# Booster_scheme.net
KiCad netlist of a schematic drawn in Altium Designer
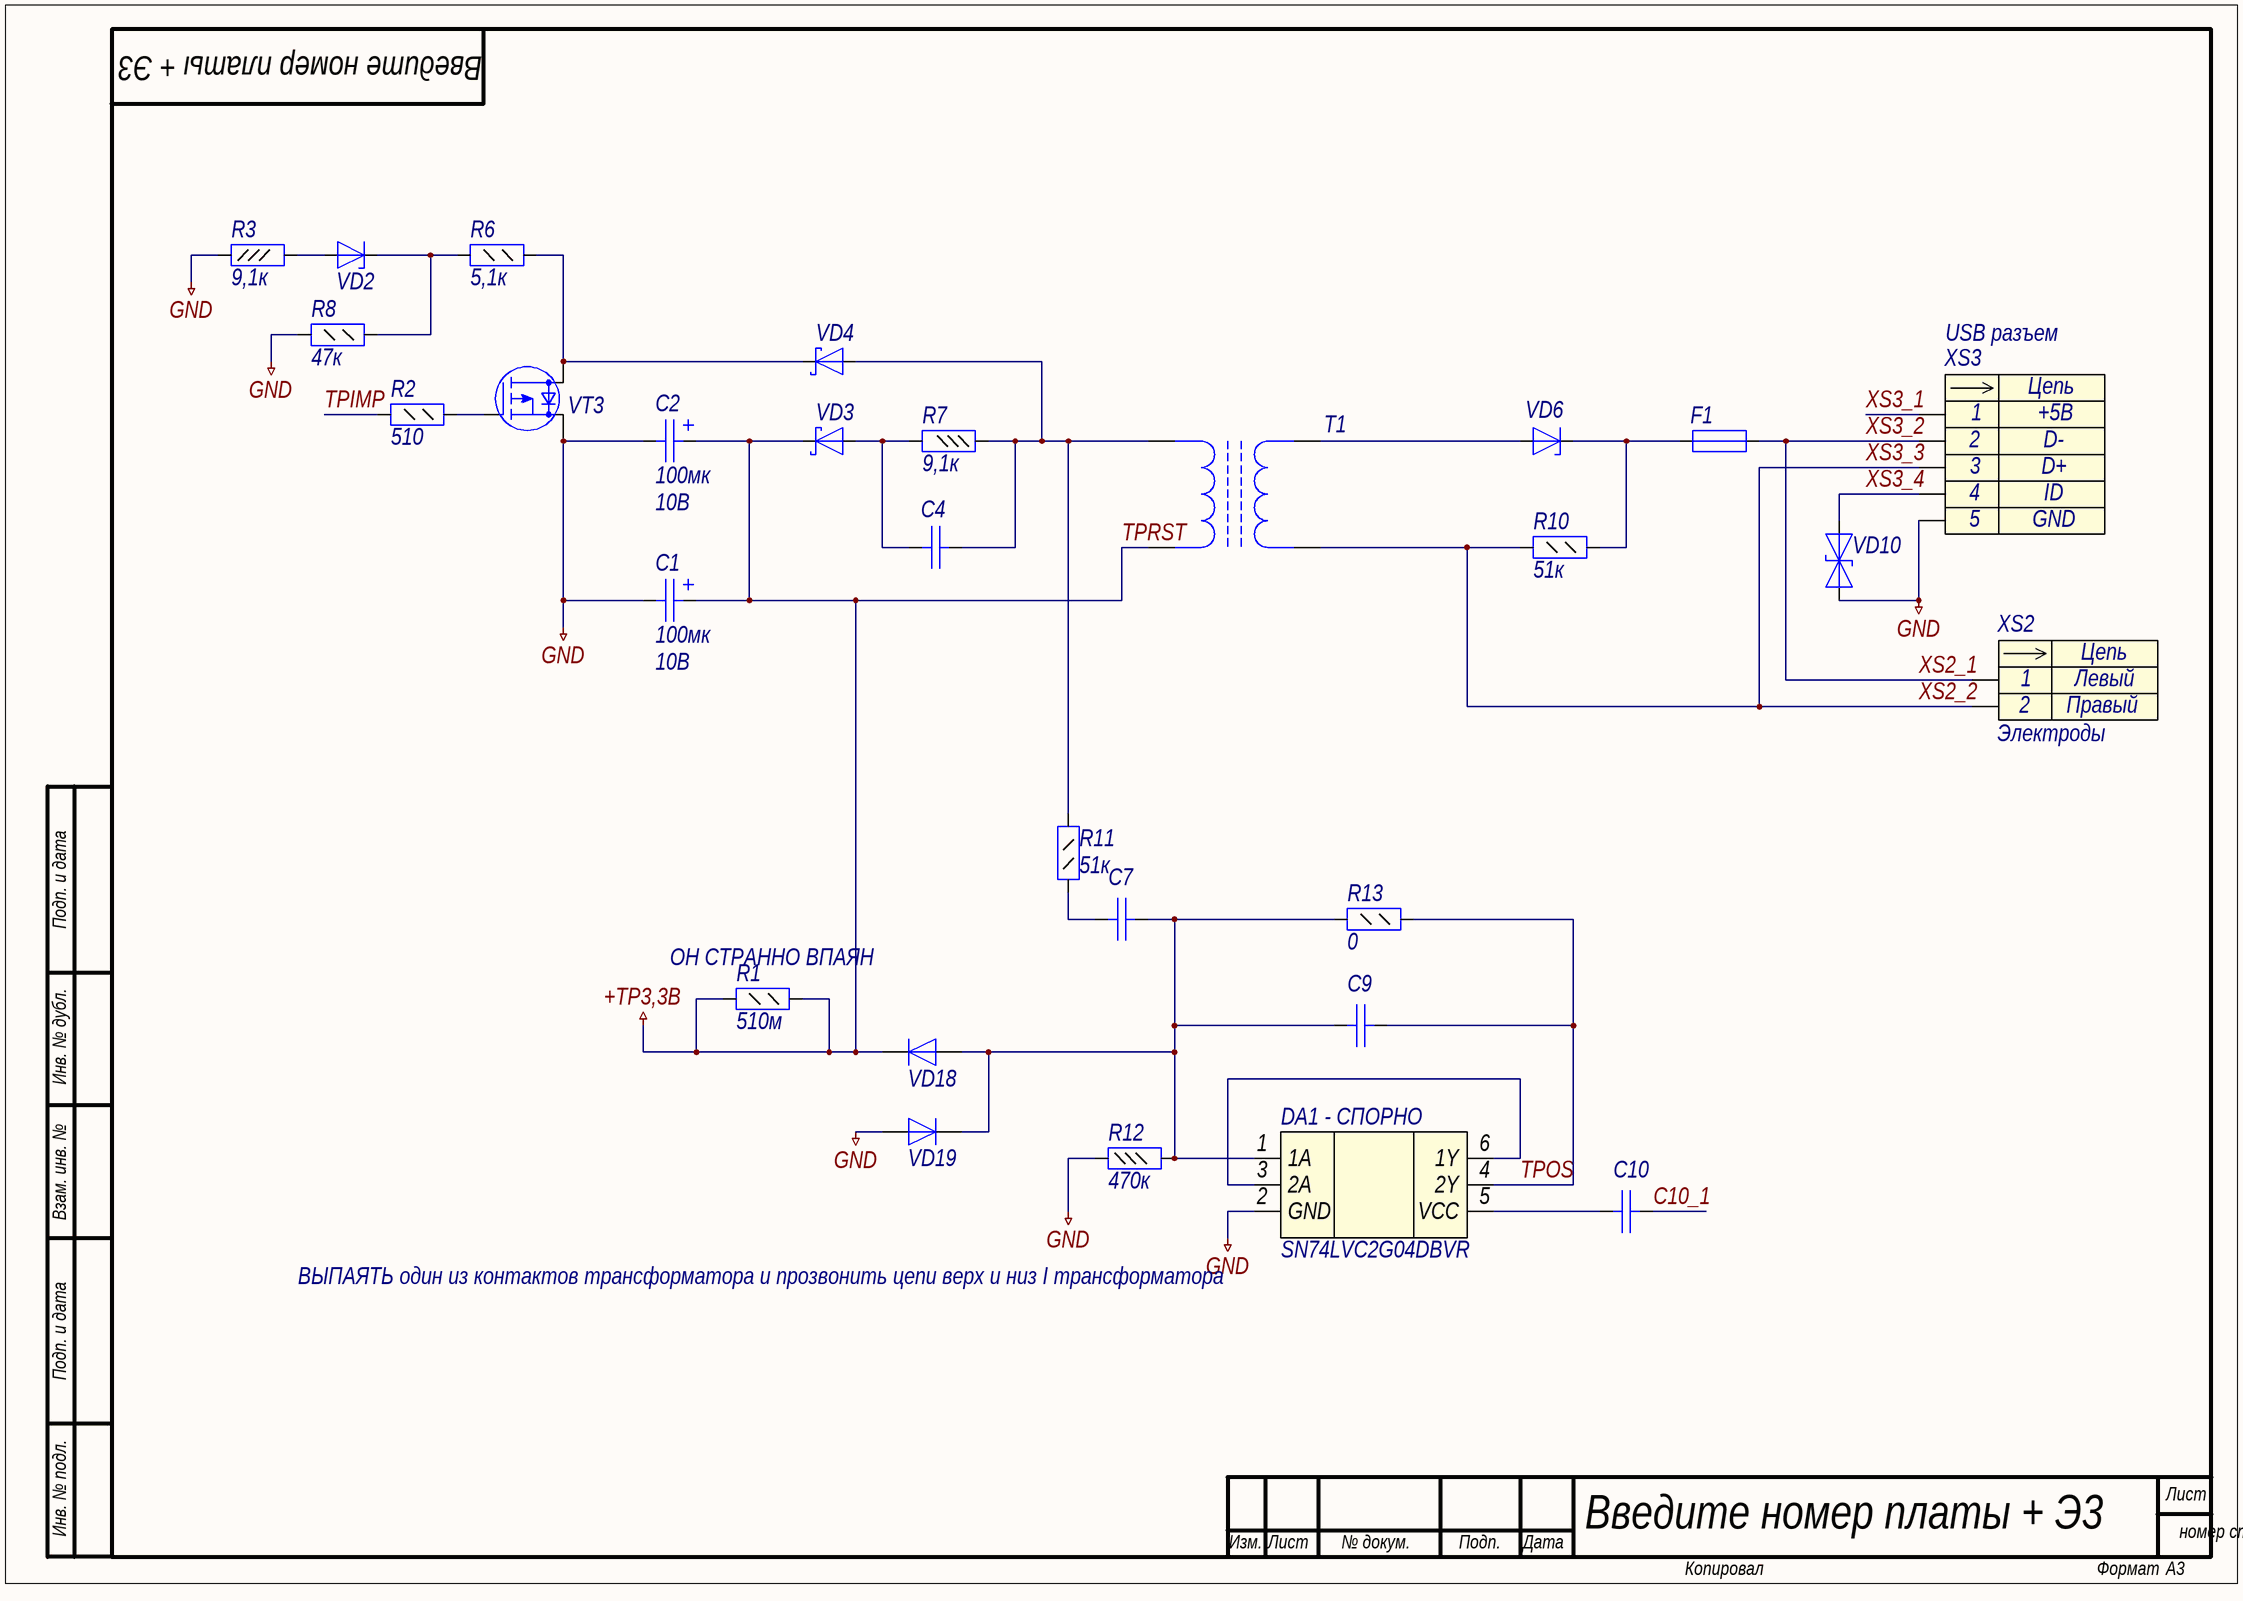
[diagram p0: Booster_scheme.SchDoc]

(export (version "E")
  (design (tool "Eeschema 10.0.6"))
  (components
    (comp (ref "C1")
      (value "100мк")
      (footprint "TANTAL CASE D")
      (description "Конденсатор полярный")
      (fields
        (field (name "VOLTAGE") "10В")
        (field (name "PART NUMBER") "T495D107K010ATA080")
        (field (name "Comment") "Capacitor_pol")
      )
      (libsource (lib "MOP44") (part "Capacitor_pol"))
    )
    (comp (ref "C2")
      (value "100мк")
      (footprint "TANTAL CASE D")
      (description "Конденсатор полярный")
      (fields
        (field (name "VOLTAGE") "10В")
        (field (name "PART NUMBER") "T495D107K010ATA080")
        (field (name "Comment") "Capacitor_pol")
      )
      (libsource (lib "MOP44") (part "Capacitor_pol"))
    )
    (comp (ref "C4")
      (value "Capacitor")
      (footprint "C0402")
      (description "Конденсатор")
      (fields (field (name "VOLTAGE") "50B") (field (name "PART NUMBER") "GRP1555C1HR47CZ01E"))
      (libsource (lib "MOP44") (part "Capacitor"))
    )
    (comp (ref "C7")
      (value "Capacitor")
      (footprint "C0402")
      (description "Конденсатор")
      (fields (field (name "VOLTAGE") "50B") (field (name "PART NUMBER") "GRP1555C1HR47CZ01E"))
      (libsource (lib "MOP44") (part "Capacitor"))
    )
    (comp (ref "C9")
      (value "Capacitor")
      (footprint "C0402")
      (description "Конденсатор")
      (fields (field (name "VOLTAGE") "50B") (field (name "PART NUMBER") "GRP1555C1HR47CZ01E"))
      (libsource (lib "MOP44") (part "Capacitor"))
    )
    (comp (ref "C10")
      (value "Capacitor")
      (footprint "C0402")
      (description "Конденсатор")
      (fields (field (name "VOLTAGE") "50B") (field (name "PART NUMBER") "GRP1555C1HR47CZ01E"))
      (libsource (lib "MOP44") (part "Capacitor"))
    )
    (comp (ref "DA1 - СПОРНО")
      (value "SN74LVC2G04DBVR")
      (footprint "SOT23-6")
      (description "Инвертирующий Триггер Шмитта")
      (fields (field (name "PART NUMBER") "SN74LVC2G04DBVR"))
      (libsource (lib "MOP44") (part "SN74LVC2G04DBVR"))
    )
    (comp (ref "F1")
      (value "Fuse")
      (footprint "FUSE812")
      (description "Предохранитель")
      (fields (field (name "PART NUMBER") "MF-MSMF050"))
      (libsource (lib "MOP44") (part "Fuse"))
    )
    (comp (ref "R1")
      (value "510м")
      (footprint "R0805")
      (description "Резистор")
      (fields (field (name "PART NUMBER") "RC0805FR-07510RL") (field (name "POWER") "0,125Вт"))
      (libsource (lib "MOP44") (part "Resistor_0,125Вт"))
    )
    (comp (ref "R2")
      (value "510")
      (footprint "R0805")
      (description "Резистор")
      (fields (field (name "PART NUMBER") "RC0805FR-07510RL") (field (name "POWER") "0,125Вт"))
      (libsource (lib "MOP44") (part "Resistor_0,125Вт"))
    )
    (comp (ref "R3")
      (value "9,1к")
      (footprint "R0603")
      (description "Резистор")
      (fields (field (name "PART NUMBER") "RC0603FR-079K1") (field (name "POWER") "0,062Вт"))
      (libsource (lib "") (part "Resistor_0,062Вт_1"))
    )
    (comp (ref "R6")
      (value "5,1к")
      (footprint "R0805")
      (description "Резистор")
      (fields (field (name "PART NUMBER") "RC0805FR-075K1") (field (name "POWER") "0,125Вт"))
      (libsource (lib "MOP44") (part "Resistor_0,125Вт"))
    )
    (comp (ref "R7")
      (value "9,1к")
      (footprint "R0603")
      (description "Резистор")
      (fields (field (name "PART NUMBER") "RC0603FR-079K1") (field (name "POWER") "0,062Вт"))
      (libsource (lib "") (part "Resistor_0,062Вт_2"))
    )
    (comp (ref "R8")
      (value "47к")
      (footprint "R0805")
      (description "Резистор")
      (fields (field (name "PART NUMBER") "RC0805FR-0747KL") (field (name "POWER") "0,125Вт"))
      (libsource (lib "MOP44") (part "Resistor_0,125Вт"))
    )
    (comp (ref "R10")
      (value "51к")
      (footprint "R0805")
      (description "Резистор")
      (fields (field (name "PART NUMBER") "RC0805FR-0751KL") (field (name "POWER") "0,125Вт"))
      (libsource (lib "MOP44") (part "Resistor_0,125Вт"))
    )
    (comp (ref "R11")
      (value "51к")
      (footprint "R0805")
      (description "Резистор")
      (fields (field (name "PART NUMBER") "RC0805FR-0751KL") (field (name "POWER") "0,125Вт"))
      (libsource (lib "") (part "Resistor_0,125Вт_1"))
    )
    (comp (ref "R12")
      (value "470к")
      (footprint "R0603")
      (description "Резистор")
      (fields (field (name "PART NUMBER") "RC0603FR-07470KL") (field (name "POWER") "0,062Вт"))
      (libsource (lib "MOP44") (part "Resistor_0,062Вт"))
    )
    (comp (ref "R13")
      (value "0")
      (footprint "R0805")
      (description "Резистор")
      (fields (field (name "PART NUMBER") "RC0805FR-070RL") (field (name "POWER") "0,125Вт"))
      (libsource (lib "MOP44") (part "Resistor_0,125Вт"))
    )
    (comp (ref "T1")
      (value "Transformer")
      (footprint "Transformer36mm")
      (description "EMI Suppression Filter")
      (libsource (lib "MOP44") (part "Transformer"))
    )
    (comp (ref "VD2")
      (value "DiodeZener")
      (footprint "SOT23-3")
      (description "Cтабилитрон (лавинный выпрямительный диод) односторонний")
      (fields (field (name "PART NUMBER") "BZX84-C30"))
      (libsource (lib "MOP44") (part "DiodeZener"))
    )
    (comp (ref "VD3")
      (value "DiodeSchottky")
      (footprint "SOD-123")
      (description "Диод Шоттки")
      (fields (field (name "PART NUMBER") "MBR0540"))
      (libsource (lib "MOP44") (part "DiodeSchottky"))
    )
    (comp (ref "VD4")
      (value "DiodeSchottky")
      (footprint "SOD-123")
      (description "Диод Шоттки")
      (fields (field (name "PART NUMBER") "MBR0540"))
      (libsource (lib "MOP44") (part "DiodeSchottky"))
    )
    (comp (ref "VD6")
      (value "DiodeZener")
      (footprint "SOT23-3")
      (description "Cтабилитрон (лавинный выпрямительный диод) односторонний")
      (fields (field (name "PART NUMBER") "BZX84-C5V1"))
      (libsource (lib "MOP44") (part "DiodeZener"))
    )
    (comp (ref "VD10")
      (value "DiodeZenerDual")
      (footprint "SMB")
      (description "Cтабилитрон (диод выпрямительный лавинный) двусторонний")
      (fields (field (name "PART NUMBER") "SMBJ8.5CA"))
      (libsource (lib "MOP44") (part "DiodeZenerDual"))
    )
    (comp (ref "VD18")
      (value "Diode")
      (footprint "SOD-123")
      (description "Диод")
      (fields (field (name "PART NUMBER") "MMSD4148"))
      (libsource (lib "MOP44") (part "Diode"))
    )
    (comp (ref "VD19")
      (value "Diode")
      (footprint "SOD-123")
      (description "Диод")
      (fields (field (name "PART NUMBER") "MMSD4148"))
      (libsource (lib "MOP44") (part "Diode"))
    )
    (comp (ref "VT3")
      (value "P-MOSFET")
      (footprint "SOT23-3")
      (description "N-MOSFET")
      (fields
        (field (name "PART NUMBER") "IRLML2244TRPbF")
        (field (name "MANUFACTURER") "International Rectifier")
      )
      (libsource (lib "MOP44") (part "P-MOSFET"))
    )
    (comp (ref "XS2")
      (value "Электроды")
      (footprint "CWF-2")
      (description "Разъем - 2 конт. вилка")
      (fields (field (name "PART NUMBER") "DS1069-2MVW6X"))
      (libsource (lib "MOP44") (part "Header_2_plg"))
    )
    (comp (ref "XS3")
      (value "USB разъем")
      (footprint "USB MINI AB RECEPTACLE")
      (description "USB Mini Type AB Receptacle")
      (fields (field (name "PART NUMBER") "UJ2-MABH-1-SMT-TR"))
      (libsource (lib "MOP44") (part "USB MINI RECEPTACLE"))
    )
  )
  (nets
    (net (code "1") (name "+TP3,3В") (class "Default")
      (node (ref "C1") (pin "1") (pinfunction "1_1") (pintype "passive"))
      (node (ref "C2") (pin "1") (pinfunction "1_1") (pintype "passive"))
      (node (ref "R1") (pin "1") (pinfunction "1_1") (pintype "passive"))
      (node (ref "R1") (pin "2") (pinfunction "2_2") (pintype "passive"))
      (node (ref "T1") (pin "2") (pinfunction "2_2") (pintype "passive"))
      (node (ref "VD18") (pin "1") (pinfunction "K_1") (pintype "passive"))
      (node (ref "VD3") (pin "1") (pinfunction "K_1") (pintype "passive"))
    )
    (net (code "2") (name "/C10_1") (class "Default")
      (node (ref "C10") (pin "1") (pinfunction "1_1") (pintype "passive"))
    )
    (net (code "3") (name "/TPIMP") (class "Default")
      (node (ref "R2") (pin "2") (pinfunction "2_2") (pintype "passive"))
    )
    (net (code "4") (name "/TPOS") (class "Default")
      (node (ref "C9") (pin "2") (pinfunction "2_2") (pintype "passive"))
      (node (ref "DA1 - СПОРНО") (pin "4") (pinfunction "2Y_4") (pintype "power_in"))
      (node (ref "R13") (pin "1") (pinfunction "1_1") (pintype "passive"))
    )
    (net (code "5") (name "/XS2_1") (class "Default")
      (node (ref "F1") (pin "1") (pinfunction "1_1") (pintype "passive"))
      (node (ref "XS2") (pin "1") (pinfunction "1_1") (pintype "passive"))
      (node (ref "XS3") (pin "2") (pinfunction "2_2") (pintype "passive"))
    )
    (net (code "6") (name "/XS2_2") (class "Default")
      (node (ref "R10") (pin "2") (pinfunction "2_2") (pintype "passive"))
      (node (ref "T1") (pin "4") (pinfunction "4_4") (pintype "passive"))
      (node (ref "XS2") (pin "2") (pinfunction "2_2") (pintype "passive"))
      (node (ref "XS3") (pin "3") (pinfunction "3_3") (pintype "passive"))
    )
    (net (code "7") (name "/XS3_1") (class "Default")
      (node (ref "XS3") (pin "1") (pinfunction "1_1") (pintype "passive"))
    )
    (net (code "8") (name "/XS3_4") (class "Default")
      (node (ref "VD10") (pin "2") (pinfunction "A_2") (pintype "passive"))
      (node (ref "XS3") (pin "4") (pinfunction "4_4") (pintype "passive"))
    )
    (net (code "9") (name "GND") (class "Default")
      (node (ref "C1") (pin "2") (pinfunction "2_2") (pintype "passive"))
      (node (ref "C2") (pin "2") (pinfunction "2_2") (pintype "passive"))
      (node (ref "DA1 - СПОРНО") (pin "2") (pinfunction "GND_2") (pintype "power_in"))
      (node (ref "R12") (pin "1") (pinfunction "1_1") (pintype "passive"))
      (node (ref "R3") (pin "1") (pinfunction "1_1") (pintype "passive"))
      (node (ref "R8") (pin "2") (pinfunction "2_2") (pintype "passive"))
      (node (ref "VD10") (pin "1") (pinfunction "K_1") (pintype "passive"))
      (node (ref "VD19") (pin "2") (pinfunction "A_2") (pintype "passive"))
      (node (ref "VT3") (pin "3") (pinfunction "S_3") (pintype "passive"))
      (node (ref "XS3") (pin "5") (pinfunction "5_5") (pintype "passive"))
    )
    (net (code "10") (name "Net-(C7-Pad2)") (class "Default")
      (node (ref "C7") (pin "2") (pinfunction "2_2") (pintype "passive"))
      (node (ref "R11") (pin "1") (pinfunction "1_1") (pintype "passive"))
    )
    (net (code "11") (name "Net-(DA1 - СПОРНО-1A)") (class "Default")
      (node (ref "C7") (pin "1") (pinfunction "1_1") (pintype "passive"))
      (node (ref "C9") (pin "1") (pinfunction "1_1") (pintype "passive"))
      (node (ref "DA1 - СПОРНО") (pin "1") (pinfunction "1A_1") (pintype "power_in"))
      (node (ref "R12") (pin "2") (pinfunction "2_2") (pintype "passive"))
      (node (ref "R13") (pin "2") (pinfunction "2_2") (pintype "passive"))
      (node (ref "VD18") (pin "2") (pinfunction "A_2") (pintype "passive"))
      (node (ref "VD19") (pin "1") (pinfunction "K_1") (pintype "passive"))
    )
    (net (code "12") (name "Net-(DA1 - СПОРНО-1Y)") (class "Default")
      (node (ref "DA1 - СПОРНО") (pin "3") (pinfunction "2A_3") (pintype "power_in"))
      (node (ref "DA1 - СПОРНО") (pin "6") (pinfunction "1Y_6") (pintype "power_in"))
    )
    (net (code "13") (name "Net-(DA1 - СПОРНО-VCC)") (class "Default")
      (node (ref "C10") (pin "2") (pinfunction "2_2") (pintype "passive"))
      (node (ref "DA1 - СПОРНО") (pin "5") (pinfunction "VCC_5") (pintype "power_in"))
    )
    (net (code "14") (name "Net-(VD2-A)") (class "Default")
      (node (ref "R3") (pin "2") (pinfunction "2_2") (pintype "passive"))
      (node (ref "VD2") (pin "2") (pinfunction "A_2") (pintype "passive"))
    )
    (net (code "15") (name "Net-(VD2-K)") (class "Default")
      (node (ref "R6") (pin "2") (pinfunction "2_2") (pintype "passive"))
      (node (ref "R8") (pin "1") (pinfunction "1_1") (pintype "passive"))
      (node (ref "VD2") (pin "1") (pinfunction "K_1") (pintype "passive"))
    )
    (net (code "16") (name "Net-(VD3-A)") (class "Default")
      (node (ref "C4") (pin "2") (pinfunction "2_2") (pintype "passive"))
      (node (ref "R7") (pin "2") (pinfunction "2_2") (pintype "passive"))
      (node (ref "VD3") (pin "2") (pinfunction "A_2") (pintype "passive"))
    )
    (net (code "17") (name "Net-(VD4-A)") (class "Default")
      (node (ref "C4") (pin "1") (pinfunction "1_1") (pintype "passive"))
      (node (ref "R11") (pin "2") (pinfunction "2_2") (pintype "passive"))
      (node (ref "R7") (pin "1") (pinfunction "1_1") (pintype "passive"))
      (node (ref "T1") (pin "1") (pinfunction "1_1") (pintype "passive"))
      (node (ref "VD4") (pin "2") (pinfunction "A_2") (pintype "passive"))
    )
    (net (code "18") (name "Net-(VD4-K)") (class "Default")
      (node (ref "R6") (pin "1") (pinfunction "1_1") (pintype "passive"))
      (node (ref "VD4") (pin "1") (pinfunction "K_1") (pintype "passive"))
      (node (ref "VT3") (pin "2") (pinfunction "D_2") (pintype "passive"))
    )
    (net (code "19") (name "Net-(VD6-A)") (class "Default")
      (node (ref "T1") (pin "3") (pinfunction "3_3") (pintype "passive"))
      (node (ref "VD6") (pin "2") (pinfunction "A_2") (pintype "passive"))
    )
    (net (code "20") (name "Net-(VD6-K)") (class "Default")
      (node (ref "F1") (pin "2") (pinfunction "2_2") (pintype "passive"))
      (node (ref "R10") (pin "1") (pinfunction "1_1") (pintype "passive"))
      (node (ref "VD6") (pin "1") (pinfunction "K_1") (pintype "passive"))
    )
    (net (code "21") (name "Net-(VT3-G)") (class "Default")
      (node (ref "R2") (pin "1") (pinfunction "1_1") (pintype "passive"))
      (node (ref "VT3") (pin "1") (pinfunction "G_1") (pintype "passive"))
    )
    (net (code "22") (name "unconnected-(T1-Pad1)") (class "Default")
      (node (ref "T1") (pin "1") (pinfunction "1_1") (pintype "passive"))
    )
    (net (code "23") (name "unconnected-(T1-Pad1)_1") (class "Default")
      (node (ref "T1") (pin "1") (pinfunction "1_1") (pintype "passive"))
    )
    (net (code "24") (name "unconnected-(T1-Pad2)") (class "Default")
      (node (ref "T1") (pin "2") (pinfunction "2_2") (pintype "passive"))
    )
    (net (code "25") (name "unconnected-(T1-Pad2)_1") (class "Default")
      (node (ref "T1") (pin "2") (pinfunction "2_2") (pintype "passive"))
    )
  )
)
